# TMP421_Temperature_Sensor.net
KiCad netlist of a schematic drawn in Altium Designer
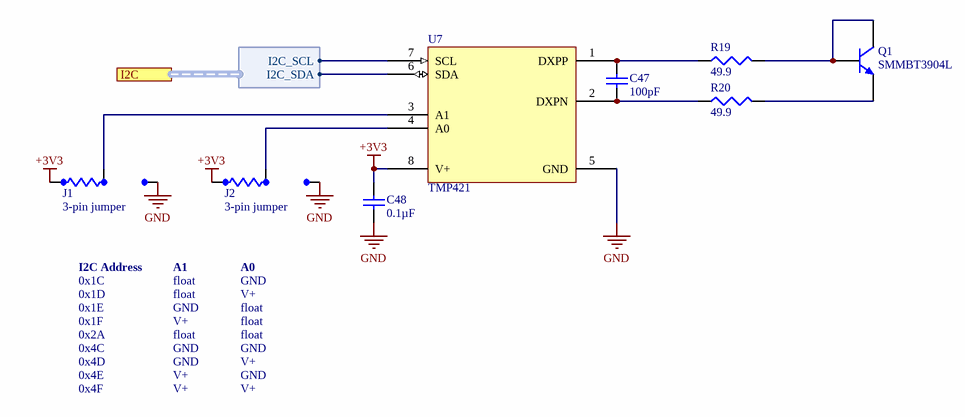
[diagram p0: TMP421 Temperature Sensor.SchDoc]

(export (version "E")
  (design (tool "Eeschema 10.0.6"))
  (components
    (comp (ref "C47")
      (value "100pF")
      (footprint "TDK-CGA2B")
      (description "CAP CER 100PF 100V C0G 0402")
      (fields
        (field (name "PART NUMBER") "PC-TDK-01226")
        (field (name "MANUFACTURER PART NUMBER") "CGA2B2C0G2A101J050BA")
        (field (name "PUBLISHER") "AlbertaSat")
      )
      (libsource (lib "Database") (part "Cap"))
    )
    (comp (ref "C48")
      (value "0.1µF")
      (footprint "TDK-CGA2B")
      (description "CAP CER 0.1UF 50V X7R 0402")
      (fields
        (field (name "PART NUMBER") "PC-TDK-02259")
        (field (name "MANUFACTURER PART NUMBER") "CGA2B3X7R1H104K050BB")
        (field (name "PUBLISHER") "AlbertaSat")
      )
      (libsource (lib "Database") (part "Cap"))
    )
    (comp (ref "J1")
      (value "3-pin jumper")
      (footprint "PANA-ERJ3EK(3-pin jumper)")
      (fields (field (name "PART NUMBER") "19867"))
      (libsource (lib "Database") (part "3-pin jumper"))
    )
    (comp (ref "J2")
      (value "3-pin jumper")
      (footprint "PANA-ERJ3EK(3-pin jumper)")
      (fields (field (name "PART NUMBER") "19867"))
      (libsource (lib "Database") (part "3-pin jumper"))
    )
    (comp (ref "Q1")
      (value "SMMBT3904L")
      (footprint "ONS-318-08")
      (description "TRANS NPN 40V 0.2A SOT23")
      (fields
        (field (name "PART NUMBER") "PU-ONS-00001")
        (field (name "MANUFACTURER PART NUMBER") "SMMBT3904LT1G")
        (field (name "PUBLISHER") "AlbertaSat")
      )
      (libsource (lib "Database") (part "SMMBT3904L"))
    )
    (comp (ref "R19")
      (value "49.9")
      (footprint "PANA-ERA2A")
      (description "RES SMD 49.9 OHM 0.1% 1/16W 0402")
      (fields
        (field (name "PART NUMBER") "13731")
        (field (name "MANUFACTURER PART NUMBER") "ERA-2AEB49R9X")
        (field (name "PUBLISHER") "Altium Limited")
      )
      (libsource (lib "Database") (part "Res3"))
    )
    (comp (ref "R20")
      (value "49.9")
      (footprint "PANA-ERA2A")
      (description "RES SMD 49.9 OHM 0.1% 1/16W 0402")
      (fields
        (field (name "PART NUMBER") "13731")
        (field (name "MANUFACTURER PART NUMBER") "ERA-2AEB49R9X")
        (field (name "PUBLISHER") "Altium Limited")
      )
      (libsource (lib "Database") (part "Res3"))
    )
    (comp (ref "U7")
      (value "TMP421")
      (footprint "TI-DCN")
      (description "SENSOR TEMPERATURE SMBUS SOT23-8")
      (fields (field (name "PART NUMBER") "40") (field (name "MANUFACTURER PART NUMBER") "TMP421AIDCNR"))
      (libsource (lib "Database") (part "TMP421"))
    )
  )
  (nets
    (net (code "2") (name "+3V3") (class "Default")
      (node (ref "C48") (pin "1") (pinfunction "1_1") (pintype "passive"))
      (node (ref "J1") (pin "3") (pinfunction "3_3") (pintype "passive"))
      (node (ref "J2") (pin "3") (pinfunction "3_3") (pintype "passive"))
      (node (ref "U7") (pin "8") (pinfunction "V+_8") (pintype "power_in"))
    )
    (net (code "3") (name "/I2C_SCL") (class "Default")
      (node (ref "U7") (pin "7") (pinfunction "SCL_7") (pintype "input"))
    )
    (net (code "4") (name "/I2C_SDA") (class "Default")
      (node (ref "U7") (pin "6") (pinfunction "SDA_6") (pintype "bidirectional"))
    )
    (net (code "6") (name "GND") (class "Default")
      (node (ref "C48") (pin "2") (pinfunction "2_2") (pintype "passive"))
      (node (ref "J1") (pin "1") (pinfunction "1_1") (pintype "passive"))
      (node (ref "J2") (pin "1") (pinfunction "1_1") (pintype "passive"))
      (node (ref "U7") (pin "5") (pinfunction "GND_5") (pintype "power_in"))
    )
    (net (code "7") (name "Net-(Q1-B)") (class "Default")
      (node (ref "Q1") (pin "1") (pinfunction "B_1") (pintype "passive"))
      (node (ref "Q1") (pin "3") (pinfunction "C_3") (pintype "passive"))
      (node (ref "R19") (pin "2") (pinfunction "2_2") (pintype "passive"))
    )
    (net (code "8") (name "Net-(Q1-E)") (class "Default")
      (node (ref "Q1") (pin "2") (pinfunction "E_2") (pintype "passive"))
      (node (ref "R20") (pin "2") (pinfunction "2_2") (pintype "passive"))
    )
    (net (code "9") (name "Net-(U7-A0)") (class "Default")
      (node (ref "J2") (pin "2") (pinfunction "2_2") (pintype "passive"))
      (node (ref "U7") (pin "4") (pinfunction "A0_4") (pintype "passive"))
    )
    (net (code "10") (name "Net-(U7-A1)") (class "Default")
      (node (ref "J1") (pin "2") (pinfunction "2_2") (pintype "passive"))
      (node (ref "U7") (pin "3") (pinfunction "A1_3") (pintype "passive"))
    )
    (net (code "11") (name "Net-(U7-DXPN)") (class "Default")
      (node (ref "C47") (pin "1") (pinfunction "1_1") (pintype "passive"))
      (node (ref "R20") (pin "1") (pinfunction "1_1") (pintype "passive"))
      (node (ref "U7") (pin "2") (pinfunction "DXPN_2") (pintype "passive"))
    )
    (net (code "12") (name "Net-(U7-DXPP)") (class "Default")
      (node (ref "C47") (pin "2") (pinfunction "2_2") (pintype "passive"))
      (node (ref "R19") (pin "1") (pinfunction "1_1") (pintype "passive"))
      (node (ref "U7") (pin "1") (pinfunction "DXPP_1") (pintype "passive"))
    )
  )
)
